# Power.net
KiCad netlist of a schematic drawn in Altium Designer
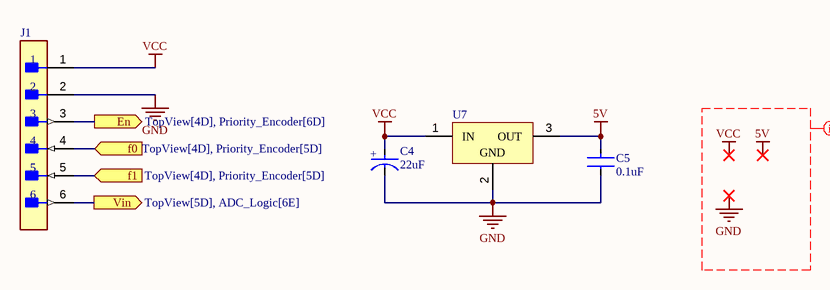
[diagram p0: Power.SchDoc]

(export (version "E")
  (design (tool "Eeschema 10.0.6"))
  (components
    (comp (ref "C4")
      (value "22uF")
      (footprint "FP-RAD-TH-D_5_0_5-L_11_1-MFG")
      (description "Aluminum Electrolytic Capacitors (Radial Lead Type) AEC-Q200 Qualified 22uF ±20% 50V")
      (fields (field (name "TOLERANCE") "20%"))
      (libsource (lib "Altium Content Vault") (part "a00bbbee19879c290e62620ae7e47b1"))
    )
    (comp (ref "C5")
      (value "0.1uF")
      (footprint "FP-K15H5-MFG")
      (description "CAP CER 0.1UF 50V X7R RADIAL")
      (fields (field (name "TOLERANCE") "10%") (field (name "VOLTAGE") "50V"))
      (libsource (lib "Altium Content Vault") (part "02cd4be3c70576c341d710602a673aa"))
    )
    (comp (ref "J1")
      (value "22-28-4060")
      (footprint "FP-22-28-4060-MFG")
      (description "CONN HEADER VERT 6POS 2.54MM")
      (libsource (lib "Altium Content Vault") (part "f2cb566baf1c37ab5a3b8e90bbeafd6"))
    )
    (comp (ref "U7")
      (value "MC7805CTG")
      (footprint "ONSC-TO-220-3-221AB-01")
      (description "Positive Voltage Regulator, 1 A, 5 V, 0 to 125 degC, 3-Pin TO-220, RoHS, Tube")
      (fields (field (name "MANUFACTURER") "ON Semiconductor"))
      (libsource (lib "Altium Content Vault") (part "ONSC-MC7805CTG-TO-220-3"))
    )
  )
  (nets
    (net (code "1") (name "/En") (class "Default")
      (node (ref "J1") (pin "3") (pinfunction "3_3") (pintype "output"))
    )
    (net (code "2") (name "/Vin") (class "Default")
      (node (ref "J1") (pin "6") (pinfunction "6_6") (pintype "output"))
    )
    (net (code "3") (name "/f0") (class "Default")
      (node (ref "J1") (pin "4") (pinfunction "4_4") (pintype "input"))
    )
    (net (code "4") (name "/f1") (class "Default")
      (node (ref "J1") (pin "5") (pinfunction "5_5") (pintype "input"))
    )
    (net (code "5") (name "5V") (class "Default")
      (node (ref "C5") (pin "1") (pinfunction "1_1") (pintype "passive"))
      (node (ref "U7") (pin "3") (pinfunction "OUT_3") (pintype "power_in"))
    )
    (net (code "6") (name "GND") (class "Default")
      (node (ref "C4") (pin "1") (pinfunction "C_1") (pintype "passive"))
      (node (ref "C5") (pin "2") (pinfunction "2_2") (pintype "passive"))
      (node (ref "J1") (pin "2") (pinfunction "2_2") (pintype "power_in"))
      (node (ref "U7") (pin "2") (pinfunction "GND_2") (pintype "power_in"))
    )
    (net (code "7") (name "VCC") (class "Default")
      (node (ref "C4") (pin "2") (pinfunction "A_2") (pintype "passive"))
      (node (ref "J1") (pin "1") (pinfunction "1_1") (pintype "power_in"))
      (node (ref "U7") (pin "1") (pinfunction "IN_1") (pintype "power_in"))
    )
  )
)
